# AQETHBluePill_w_RESET.net
KiCad netlist of a schematic drawn in EAGLE
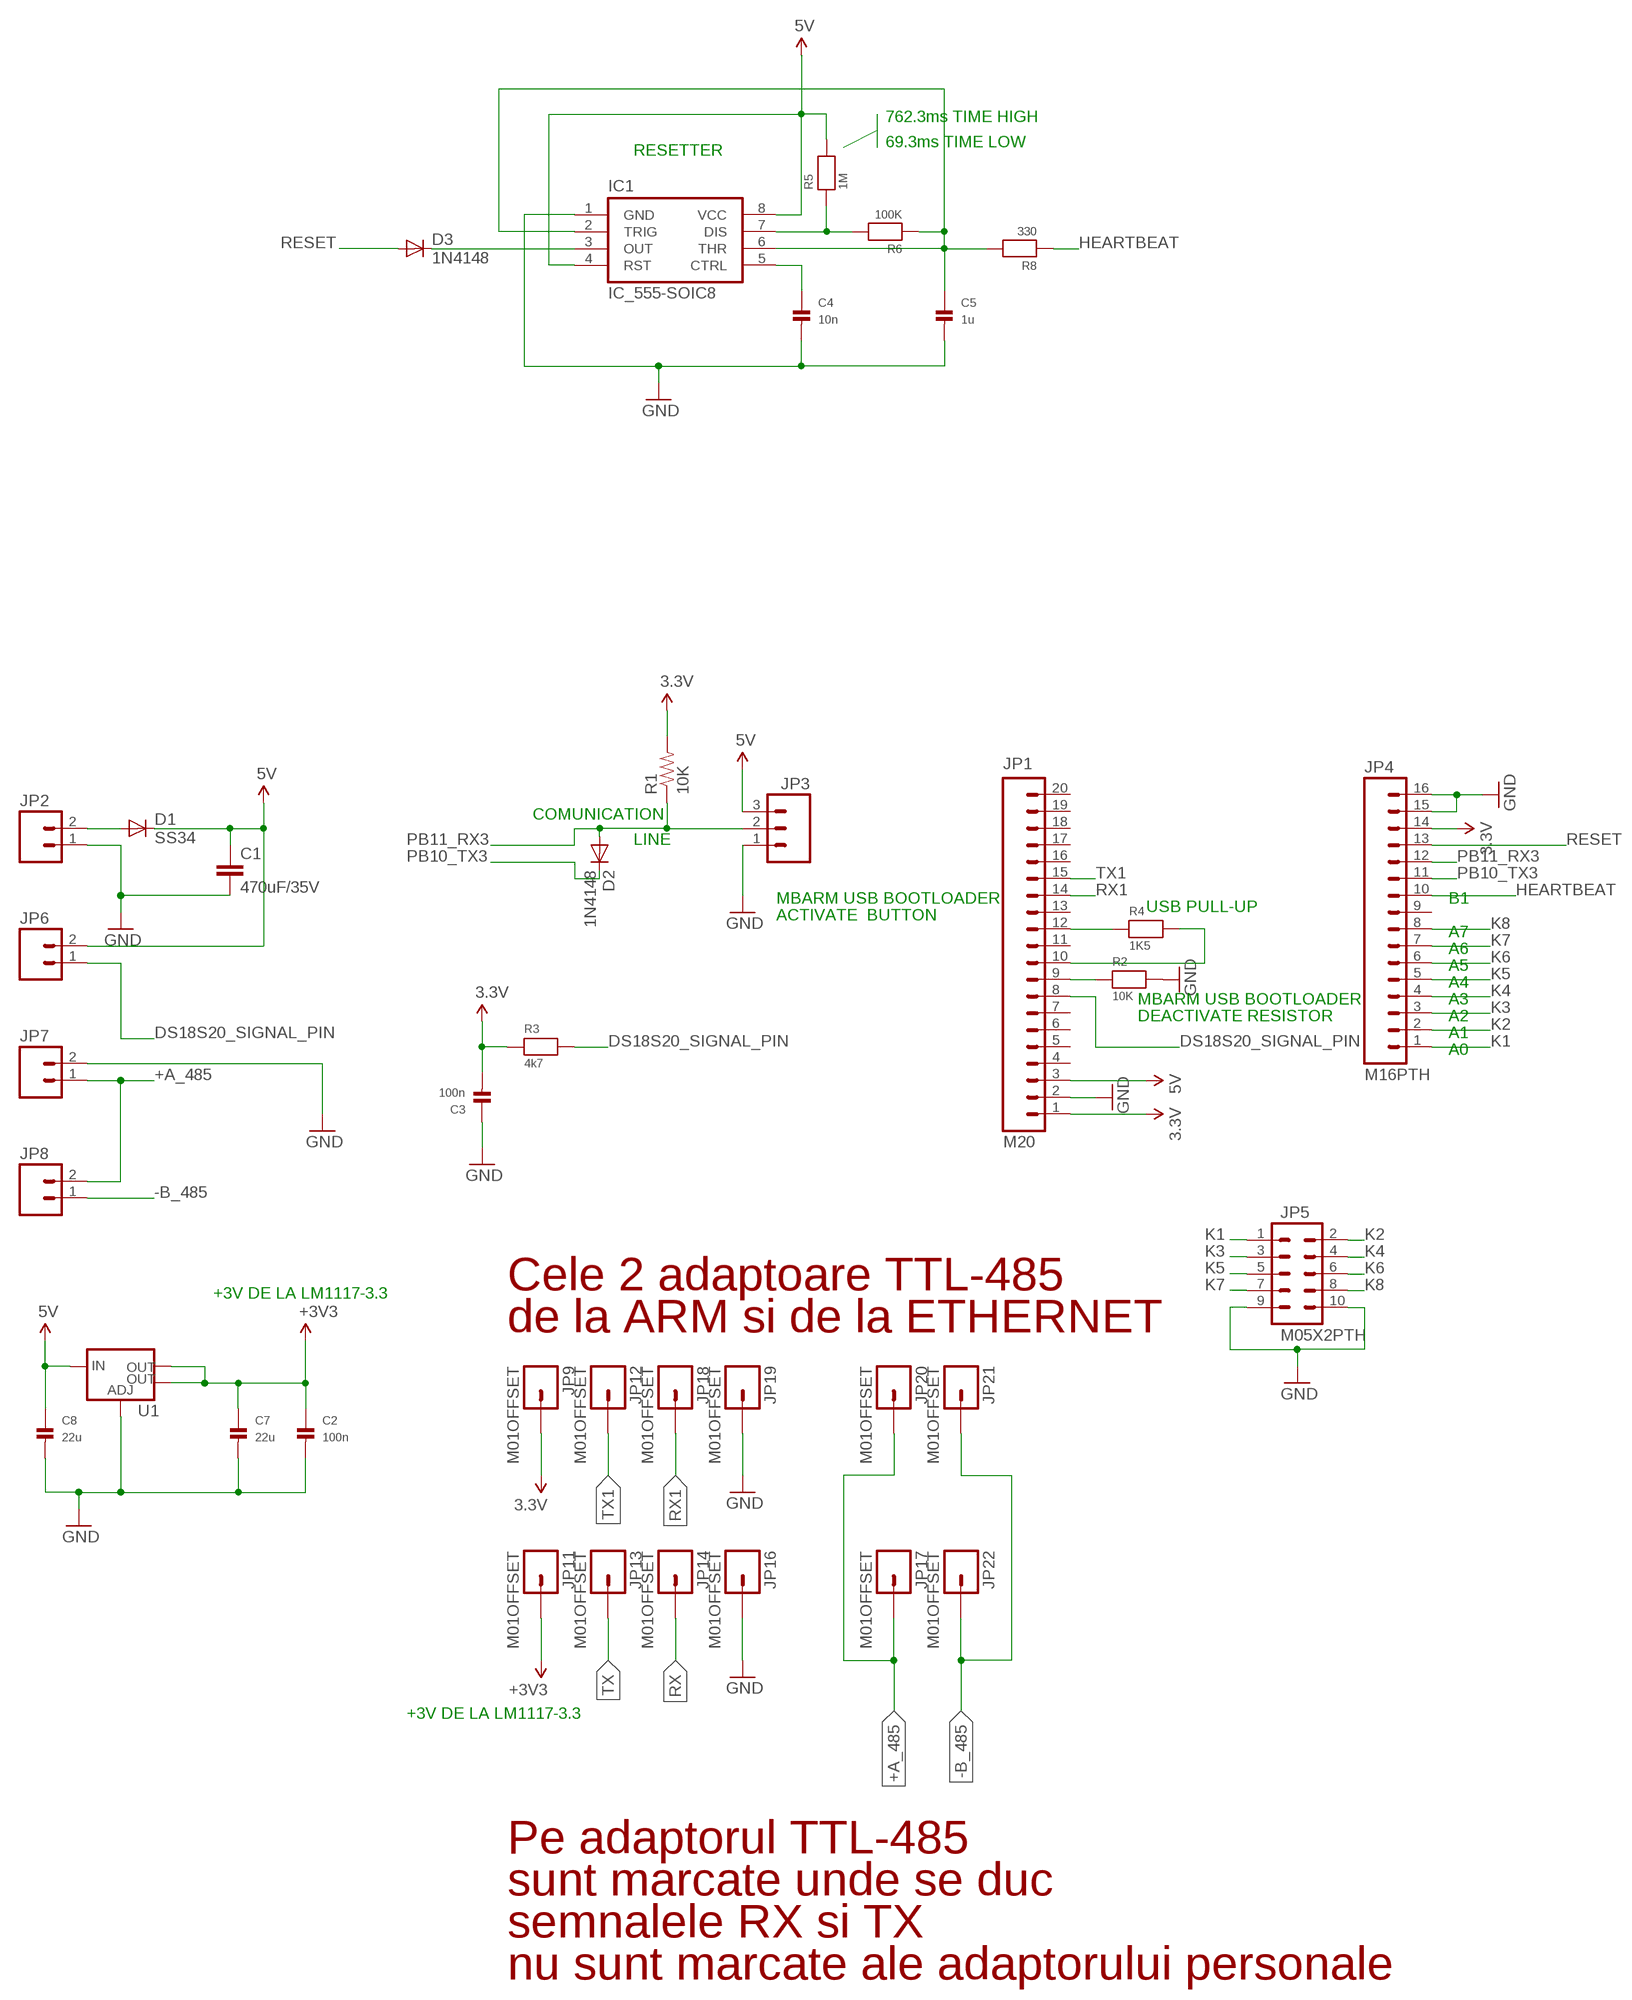
[diagram p0: schematic, sheet 1]

(export (version "E")
  (design (tool "Eeschema 10.0.6"))
  (components
    (comp (ref "C1")
      (value "470uF/35V")
      (footprint "eagle-import:CAP-PTH-5MM")
      (libsource (lib "eagle-import") (part "CAPPTH1"))
    )
    (comp (ref "C2")
      (value "100n")
      (footprint "eagle-import:_0805MP")
      (libsource (lib "eagle-import") (part "CAP_CERAMIC_0805MP"))
    )
    (comp (ref "C3")
      (value "100n")
      (footprint "eagle-import:_0805MP")
      (libsource (lib "eagle-import") (part "CAP_CERAMIC_0805MP"))
    )
    (comp (ref "C4")
      (value "10n")
      (footprint "eagle-import:_0805MP")
      (libsource (lib "eagle-import") (part "CAP_CERAMIC_0805MP"))
    )
    (comp (ref "C5")
      (value "1u")
      (footprint "eagle-import:1206")
      (libsource (lib "eagle-import") (part "CAP_CERAMIC1206"))
    )
    (comp (ref "C7")
      (value "22u")
      (footprint "eagle-import:1206")
      (libsource (lib "eagle-import") (part "CAP_CERAMIC1206"))
    )
    (comp (ref "C8")
      (value "22u")
      (footprint "eagle-import:1206")
      (libsource (lib "eagle-import") (part "CAP_CERAMIC1206"))
    )
    (comp (ref "D1")
      (value "SS34")
      (footprint "eagle-import:SMC")
      (libsource (lib "eagle-import") (part "DIODE-SMC"))
    )
    (comp (ref "D2")
      (value "1N4148")
      (footprint "eagle-import:MINIMELF")
      (libsource (lib "eagle-import") (part "DIODE-MINIMELF"))
    )
    (comp (ref "D3")
      (value "1N4148")
      (footprint "eagle-import:MINIMELF")
      (libsource (lib "eagle-import") (part "DIODE-MINIMELF"))
    )
    (comp (ref "IC1")
      (value "IC_555-SOIC8")
      (footprint "eagle-import:SOIC-8")
      (libsource (lib "eagle-import") (part "IC_555-SOIC8"))
    )
    (comp (ref "JP1")
      (value "M20")
      (footprint "eagle-import:1X20")
      (libsource (lib "eagle-import") (part "M20"))
    )
    (comp (ref "JP2")
      (value "M025MM")
      (footprint "eagle-import:SCREWTERMINAL-5MM-2")
      (libsource (lib "eagle-import") (part "M025MM"))
    )
    (comp (ref "JP3")
      (value "M03LOCK_LONGPADS")
      (footprint "eagle-import:1X03_LOCK_LONGPADS")
      (libsource (lib "eagle-import") (part "M03LOCK_LONGPADS"))
    )
    (comp (ref "JP4")
      (value "M16PTH")
      (footprint "eagle-import:1X16")
      (libsource (lib "eagle-import") (part "M16PTH"))
    )
    (comp (ref "JP5")
      (value "M05X2PTH")
      (footprint "eagle-import:AVR_ICSP")
      (libsource (lib "eagle-import") (part "M05X2PTH"))
    )
    (comp (ref "JP6")
      (value "M025MM")
      (footprint "eagle-import:SCREWTERMINAL-5MM-2")
      (libsource (lib "eagle-import") (part "M025MM"))
    )
    (comp (ref "JP7")
      (value "M025MM")
      (footprint "eagle-import:SCREWTERMINAL-5MM-2")
      (libsource (lib "eagle-import") (part "M025MM"))
    )
    (comp (ref "JP8")
      (value "M025MM")
      (footprint "eagle-import:SCREWTERMINAL-5MM-2")
      (libsource (lib "eagle-import") (part "M025MM"))
    )
    (comp (ref "JP9")
      (value "M01OFFSET")
      (footprint "eagle-import:1X01_OFFSET")
      (libsource (lib "eagle-import") (part "M01OFFSET"))
    )
    (comp (ref "JP11")
      (value "M01OFFSET")
      (footprint "eagle-import:1X01_OFFSET")
      (libsource (lib "eagle-import") (part "M01OFFSET"))
    )
    (comp (ref "JP12")
      (value "M01OFFSET")
      (footprint "eagle-import:1X01_OFFSET")
      (libsource (lib "eagle-import") (part "M01OFFSET"))
    )
    (comp (ref "JP13")
      (value "M01OFFSET")
      (footprint "eagle-import:1X01_OFFSET")
      (libsource (lib "eagle-import") (part "M01OFFSET"))
    )
    (comp (ref "JP14")
      (value "M01OFFSET")
      (footprint "eagle-import:1X01_OFFSET")
      (libsource (lib "eagle-import") (part "M01OFFSET"))
    )
    (comp (ref "JP16")
      (value "M01OFFSET")
      (footprint "eagle-import:1X01_OFFSET")
      (libsource (lib "eagle-import") (part "M01OFFSET"))
    )
    (comp (ref "JP17")
      (value "M01OFFSET")
      (footprint "eagle-import:1X01_OFFSET")
      (libsource (lib "eagle-import") (part "M01OFFSET"))
    )
    (comp (ref "JP18")
      (value "M01OFFSET")
      (footprint "eagle-import:1X01_OFFSET")
      (libsource (lib "eagle-import") (part "M01OFFSET"))
    )
    (comp (ref "JP19")
      (value "M01OFFSET")
      (footprint "eagle-import:1X01_OFFSET")
      (libsource (lib "eagle-import") (part "M01OFFSET"))
    )
    (comp (ref "JP20")
      (value "M01OFFSET")
      (footprint "eagle-import:1X01_OFFSET")
      (libsource (lib "eagle-import") (part "M01OFFSET"))
    )
    (comp (ref "JP21")
      (value "M01OFFSET")
      (footprint "eagle-import:1X01_OFFSET")
      (libsource (lib "eagle-import") (part "M01OFFSET"))
    )
    (comp (ref "JP22")
      (value "M01OFFSET")
      (footprint "eagle-import:1X01_OFFSET")
      (libsource (lib "eagle-import") (part "M01OFFSET"))
    )
    (comp (ref "R1")
      (value "10K")
      (footprint "eagle-import:1206")
      (libsource (lib "eagle-import") (part "RESISTOR1206"))
    )
    (comp (ref "R2")
      (value "10K")
      (footprint "eagle-import:_0805MP")
      (libsource (lib "eagle-import") (part "RESISTOR_0805MP"))
    )
    (comp (ref "R3")
      (value "4k7")
      (footprint "eagle-import:_0805MP")
      (libsource (lib "eagle-import") (part "RESISTOR_0805MP"))
    )
    (comp (ref "R4")
      (value "1K5")
      (footprint "eagle-import:_0805MP")
      (libsource (lib "eagle-import") (part "RESISTOR_0805MP"))
    )
    (comp (ref "R5")
      (value "1M")
      (footprint "eagle-import:_0805MP")
      (libsource (lib "eagle-import") (part "RESISTOR_0805MP"))
    )
    (comp (ref "R6")
      (value "100K")
      (footprint "eagle-import:_0805MP")
      (libsource (lib "eagle-import") (part "RESISTOR_0805MP"))
    )
    (comp (ref "R8")
      (value "330")
      (footprint "eagle-import:_0805MP")
      (libsource (lib "eagle-import") (part "RESISTOR_0805MP"))
    )
    (comp (ref "U1")
      (value "V_REG_LM1117SOT223")
      (footprint "eagle-import:SOT223")
      (libsource (lib "eagle-import") (part "V_REG_LM1117SOT223"))
    )
  )
  (nets
    (net (code "1") (name "+3V3") (class "Default")
      (node (ref "C2") (pin "1") (pinfunction "P$1_1") (pintype "passive"))
      (node (ref "C7") (pin "1") (pinfunction "P$1_1") (pintype "passive"))
      (node (ref "JP11") (pin "1") (pinfunction "1_1") (pintype "passive"))
      (node (ref "U1") (pin "2") (pinfunction "OUT_2") (pintype "output"))
      (node (ref "U1") (pin "4") (pinfunction "OUT_4") (pintype "output"))
    )
    (net (code "2") (name "+A_485") (class "Default")
      (node (ref "JP17") (pin "1") (pinfunction "1_1") (pintype "passive"))
      (node (ref "JP20") (pin "1") (pinfunction "1_1") (pintype "passive"))
      (node (ref "JP7") (pin "1") (pinfunction "1_1") (pintype "passive"))
      (node (ref "JP8") (pin "2") (pinfunction "2_2") (pintype "passive"))
    )
    (net (code "3") (name "-B_485") (class "Default")
      (node (ref "JP21") (pin "1") (pinfunction "1_1") (pintype "passive"))
      (node (ref "JP22") (pin "1") (pinfunction "1_1") (pintype "passive"))
      (node (ref "JP8") (pin "1") (pinfunction "1_1") (pintype "passive"))
    )
    (net (code "4") (name "/DS18S20_SIGNAL_PIN") (class "Default")
      (node (ref "JP1") (pin "8") (pinfunction "8_8") (pintype "passive"))
      (node (ref "JP6") (pin "1") (pinfunction "1_1") (pintype "passive"))
      (node (ref "R3") (pin "2") (pinfunction "2_2") (pintype "passive"))
    )
    (net (code "5") (name "/HEARTBEAT") (class "Default")
      (node (ref "JP4") (pin "10") (pinfunction "10_10") (pintype "passive"))
      (node (ref "R8") (pin "1") (pinfunction "1_1") (pintype "passive"))
    )
    (net (code "6") (name "/K1") (class "Default")
      (node (ref "JP4") (pin "1") (pinfunction "1_1") (pintype "passive"))
      (node (ref "JP5") (pin "1") (pinfunction "1_1") (pintype "passive"))
    )
    (net (code "7") (name "/K2") (class "Default")
      (node (ref "JP4") (pin "2") (pinfunction "2_2") (pintype "passive"))
      (node (ref "JP5") (pin "2") (pinfunction "2_2") (pintype "passive"))
    )
    (net (code "8") (name "/K3") (class "Default")
      (node (ref "JP4") (pin "3") (pinfunction "3_3") (pintype "passive"))
      (node (ref "JP5") (pin "3") (pinfunction "3_3") (pintype "passive"))
    )
    (net (code "9") (name "/K4") (class "Default")
      (node (ref "JP4") (pin "4") (pinfunction "4_4") (pintype "passive"))
      (node (ref "JP5") (pin "4") (pinfunction "4_4") (pintype "passive"))
    )
    (net (code "10") (name "/K5") (class "Default")
      (node (ref "JP4") (pin "5") (pinfunction "5_5") (pintype "passive"))
      (node (ref "JP5") (pin "5") (pinfunction "5_5") (pintype "passive"))
    )
    (net (code "11") (name "/K6") (class "Default")
      (node (ref "JP4") (pin "6") (pinfunction "6_6") (pintype "passive"))
      (node (ref "JP5") (pin "6") (pinfunction "6_6") (pintype "passive"))
    )
    (net (code "12") (name "/K7") (class "Default")
      (node (ref "JP4") (pin "7") (pinfunction "7_7") (pintype "passive"))
      (node (ref "JP5") (pin "7") (pinfunction "7_7") (pintype "passive"))
    )
    (net (code "13") (name "/K8") (class "Default")
      (node (ref "JP4") (pin "8") (pinfunction "8_8") (pintype "passive"))
      (node (ref "JP5") (pin "8") (pinfunction "8_8") (pintype "passive"))
    )
    (net (code "14") (name "/PB10_TX3") (class "Default")
      (node (ref "D2") (pin "C") (pinfunction "C_C") (pintype "passive"))
      (node (ref "JP4") (pin "11") (pinfunction "11_11") (pintype "passive"))
    )
    (net (code "15") (name "/PB11_RX3") (class "Default")
      (node (ref "D2") (pin "A") (pinfunction "A_A") (pintype "passive"))
      (node (ref "JP3") (pin "2") (pinfunction "2_2") (pintype "passive"))
      (node (ref "JP4") (pin "12") (pinfunction "12_12") (pintype "passive"))
      (node (ref "R1") (pin "1") (pinfunction "1_1") (pintype "passive"))
    )
    (net (code "16") (name "/RESET") (class "Default")
      (node (ref "D3") (pin "A") (pinfunction "A_A") (pintype "passive"))
      (node (ref "JP4") (pin "13") (pinfunction "13_13") (pintype "passive"))
    )
    (net (code "17") (name "3.3V") (class "Default")
      (node (ref "C3") (pin "2") (pinfunction "P$2_2") (pintype "passive"))
      (node (ref "JP1") (pin "1") (pinfunction "1_1") (pintype "passive"))
      (node (ref "JP4") (pin "14") (pinfunction "14_14") (pintype "passive"))
      (node (ref "JP9") (pin "1") (pinfunction "1_1") (pintype "passive"))
      (node (ref "R1") (pin "2") (pinfunction "2_2") (pintype "passive"))
      (node (ref "R3") (pin "1") (pinfunction "1_1") (pintype "passive"))
    )
    (net (code "18") (name "5V") (class "Default")
      (node (ref "C1") (pin "1") (pinfunction "1_1") (pintype "passive"))
      (node (ref "C8") (pin "1") (pinfunction "P$1_1") (pintype "passive"))
      (node (ref "D1") (pin "C") (pinfunction "C_C") (pintype "passive"))
      (node (ref "IC1") (pin "4") (pinfunction "RST_4") (pintype "input"))
      (node (ref "IC1") (pin "8") (pinfunction "VCC_8") (pintype "power_in"))
      (node (ref "JP1") (pin "3") (pinfunction "3_3") (pintype "passive"))
      (node (ref "JP3") (pin "3") (pinfunction "3_3") (pintype "passive"))
      (node (ref "JP6") (pin "2") (pinfunction "2_2") (pintype "passive"))
      (node (ref "R5") (pin "2") (pinfunction "2_2") (pintype "passive"))
      (node (ref "U1") (pin "3") (pinfunction "IN_3") (pintype "input"))
    )
    (net (code "19") (name "GND") (class "Default")
      (node (ref "C1") (pin "2") (pinfunction "2_2") (pintype "passive"))
      (node (ref "C2") (pin "2") (pinfunction "P$2_2") (pintype "passive"))
      (node (ref "C3") (pin "1") (pinfunction "P$1_1") (pintype "passive"))
      (node (ref "C4") (pin "2") (pinfunction "P$2_2") (pintype "passive"))
      (node (ref "C5") (pin "2") (pinfunction "P$2_2") (pintype "passive"))
      (node (ref "C7") (pin "2") (pinfunction "P$2_2") (pintype "passive"))
      (node (ref "C8") (pin "2") (pinfunction "P$2_2") (pintype "passive"))
      (node (ref "IC1") (pin "1") (pinfunction "GND_1") (pintype "power_in"))
      (node (ref "JP1") (pin "2") (pinfunction "2_2") (pintype "passive"))
      (node (ref "JP16") (pin "1") (pinfunction "1_1") (pintype "passive"))
      (node (ref "JP19") (pin "1") (pinfunction "1_1") (pintype "passive"))
      (node (ref "JP2") (pin "1") (pinfunction "1_1") (pintype "passive"))
      (node (ref "JP3") (pin "1") (pinfunction "1_1") (pintype "passive"))
      (node (ref "JP4") (pin "15") (pinfunction "15_15") (pintype "passive"))
      (node (ref "JP4") (pin "16") (pinfunction "16_16") (pintype "passive"))
      (node (ref "JP5") (pin "10") (pinfunction "10_10") (pintype "passive"))
      (node (ref "JP5") (pin "9") (pinfunction "9_9") (pintype "passive"))
      (node (ref "JP7") (pin "2") (pinfunction "2_2") (pintype "passive"))
      (node (ref "R2") (pin "2") (pinfunction "2_2") (pintype "passive"))
      (node (ref "U1") (pin "1") (pinfunction "ADJ_1") (pintype "input"))
    )
    (net (code "20") (name "Net-(C4-P$1)") (class "Default")
      (node (ref "C4") (pin "1") (pinfunction "P$1_1") (pintype "passive"))
      (node (ref "IC1") (pin "5") (pinfunction "CTRL_5") (pintype "power_in"))
    )
    (net (code "21") (name "Net-(C5-P$1)") (class "Default")
      (node (ref "C5") (pin "1") (pinfunction "P$1_1") (pintype "passive"))
      (node (ref "IC1") (pin "2") (pinfunction "TRIG_2") (pintype "input"))
      (node (ref "IC1") (pin "6") (pinfunction "THR_6") (pintype "input"))
      (node (ref "R6") (pin "1") (pinfunction "1_1") (pintype "passive"))
      (node (ref "R8") (pin "2") (pinfunction "2_2") (pintype "passive"))
    )
    (net (code "22") (name "Net-(D1-PadA)") (class "Default")
      (node (ref "D1") (pin "A") (pinfunction "A_A") (pintype "passive"))
      (node (ref "JP2") (pin "2") (pinfunction "2_2") (pintype "passive"))
    )
    (net (code "23") (name "Net-(IC1-DIS)") (class "Default")
      (node (ref "IC1") (pin "7") (pinfunction "DIS_7") (pintype "input"))
      (node (ref "R5") (pin "1") (pinfunction "1_1") (pintype "passive"))
      (node (ref "R6") (pin "2") (pinfunction "2_2") (pintype "passive"))
    )
    (net (code "24") (name "Net-(IC1-OUT)") (class "Default")
      (node (ref "D3") (pin "C") (pinfunction "C_C") (pintype "passive"))
      (node (ref "IC1") (pin "3") (pinfunction "OUT_3") (pintype "output"))
    )
    (net (code "25") (name "Net-(JP1-Pad9)") (class "Default")
      (node (ref "JP1") (pin "9") (pinfunction "9_9") (pintype "passive"))
      (node (ref "R2") (pin "1") (pinfunction "1_1") (pintype "passive"))
    )
    (net (code "26") (name "Net-(JP1-Pad10)") (class "Default")
      (node (ref "JP1") (pin "10") (pinfunction "10_10") (pintype "passive"))
      (node (ref "R4") (pin "2") (pinfunction "2_2") (pintype "passive"))
    )
    (net (code "27") (name "Net-(JP1-Pad12)") (class "Default")
      (node (ref "JP1") (pin "12") (pinfunction "12_12") (pintype "passive"))
      (node (ref "R4") (pin "1") (pinfunction "1_1") (pintype "passive"))
    )
    (net (code "28") (name "RX") (class "Default")
      (node (ref "JP14") (pin "1") (pinfunction "1_1") (pintype "passive"))
    )
    (net (code "29") (name "RX1") (class "Default")
      (node (ref "JP1") (pin "14") (pinfunction "14_14") (pintype "passive"))
      (node (ref "JP18") (pin "1") (pinfunction "1_1") (pintype "passive"))
    )
    (net (code "30") (name "TX") (class "Default")
      (node (ref "JP13") (pin "1") (pinfunction "1_1") (pintype "passive"))
    )
    (net (code "31") (name "TX1") (class "Default")
      (node (ref "JP1") (pin "15") (pinfunction "15_15") (pintype "passive"))
      (node (ref "JP12") (pin "1") (pinfunction "1_1") (pintype "passive"))
    )
    (net (code "32") (name "unconnected-(JP1-Pad4)") (class "Default")
      (node (ref "JP1") (pin "4") (pinfunction "4_4") (pintype "passive"))
    )
    (net (code "33") (name "unconnected-(JP1-Pad5)") (class "Default")
      (node (ref "JP1") (pin "5") (pinfunction "5_5") (pintype "passive"))
    )
    (net (code "34") (name "unconnected-(JP1-Pad6)") (class "Default")
      (node (ref "JP1") (pin "6") (pinfunction "6_6") (pintype "passive"))
    )
    (net (code "35") (name "unconnected-(JP1-Pad7)") (class "Default")
      (node (ref "JP1") (pin "7") (pinfunction "7_7") (pintype "passive"))
    )
    (net (code "36") (name "unconnected-(JP1-Pad11)") (class "Default")
      (node (ref "JP1") (pin "11") (pinfunction "11_11") (pintype "passive"))
    )
    (net (code "37") (name "unconnected-(JP1-Pad13)") (class "Default")
      (node (ref "JP1") (pin "13") (pinfunction "13_13") (pintype "passive"))
    )
    (net (code "38") (name "unconnected-(JP1-Pad16)") (class "Default")
      (node (ref "JP1") (pin "16") (pinfunction "16_16") (pintype "passive"))
    )
    (net (code "39") (name "unconnected-(JP1-Pad17)") (class "Default")
      (node (ref "JP1") (pin "17") (pinfunction "17_17") (pintype "passive"))
    )
    (net (code "40") (name "unconnected-(JP1-Pad18)") (class "Default")
      (node (ref "JP1") (pin "18") (pinfunction "18_18") (pintype "passive"))
    )
    (net (code "41") (name "unconnected-(JP1-Pad19)") (class "Default")
      (node (ref "JP1") (pin "19") (pinfunction "19_19") (pintype "passive"))
    )
    (net (code "42") (name "unconnected-(JP1-Pad20)") (class "Default")
      (node (ref "JP1") (pin "20") (pinfunction "20_20") (pintype "passive"))
    )
    (net (code "43") (name "unconnected-(JP4-Pad9)") (class "Default")
      (node (ref "JP4") (pin "9") (pinfunction "9_9") (pintype "passive"))
    )
  )
)
